# Adaptador_de_Iluminacao.net
KiCad netlist of a schematic drawn in EAGLE
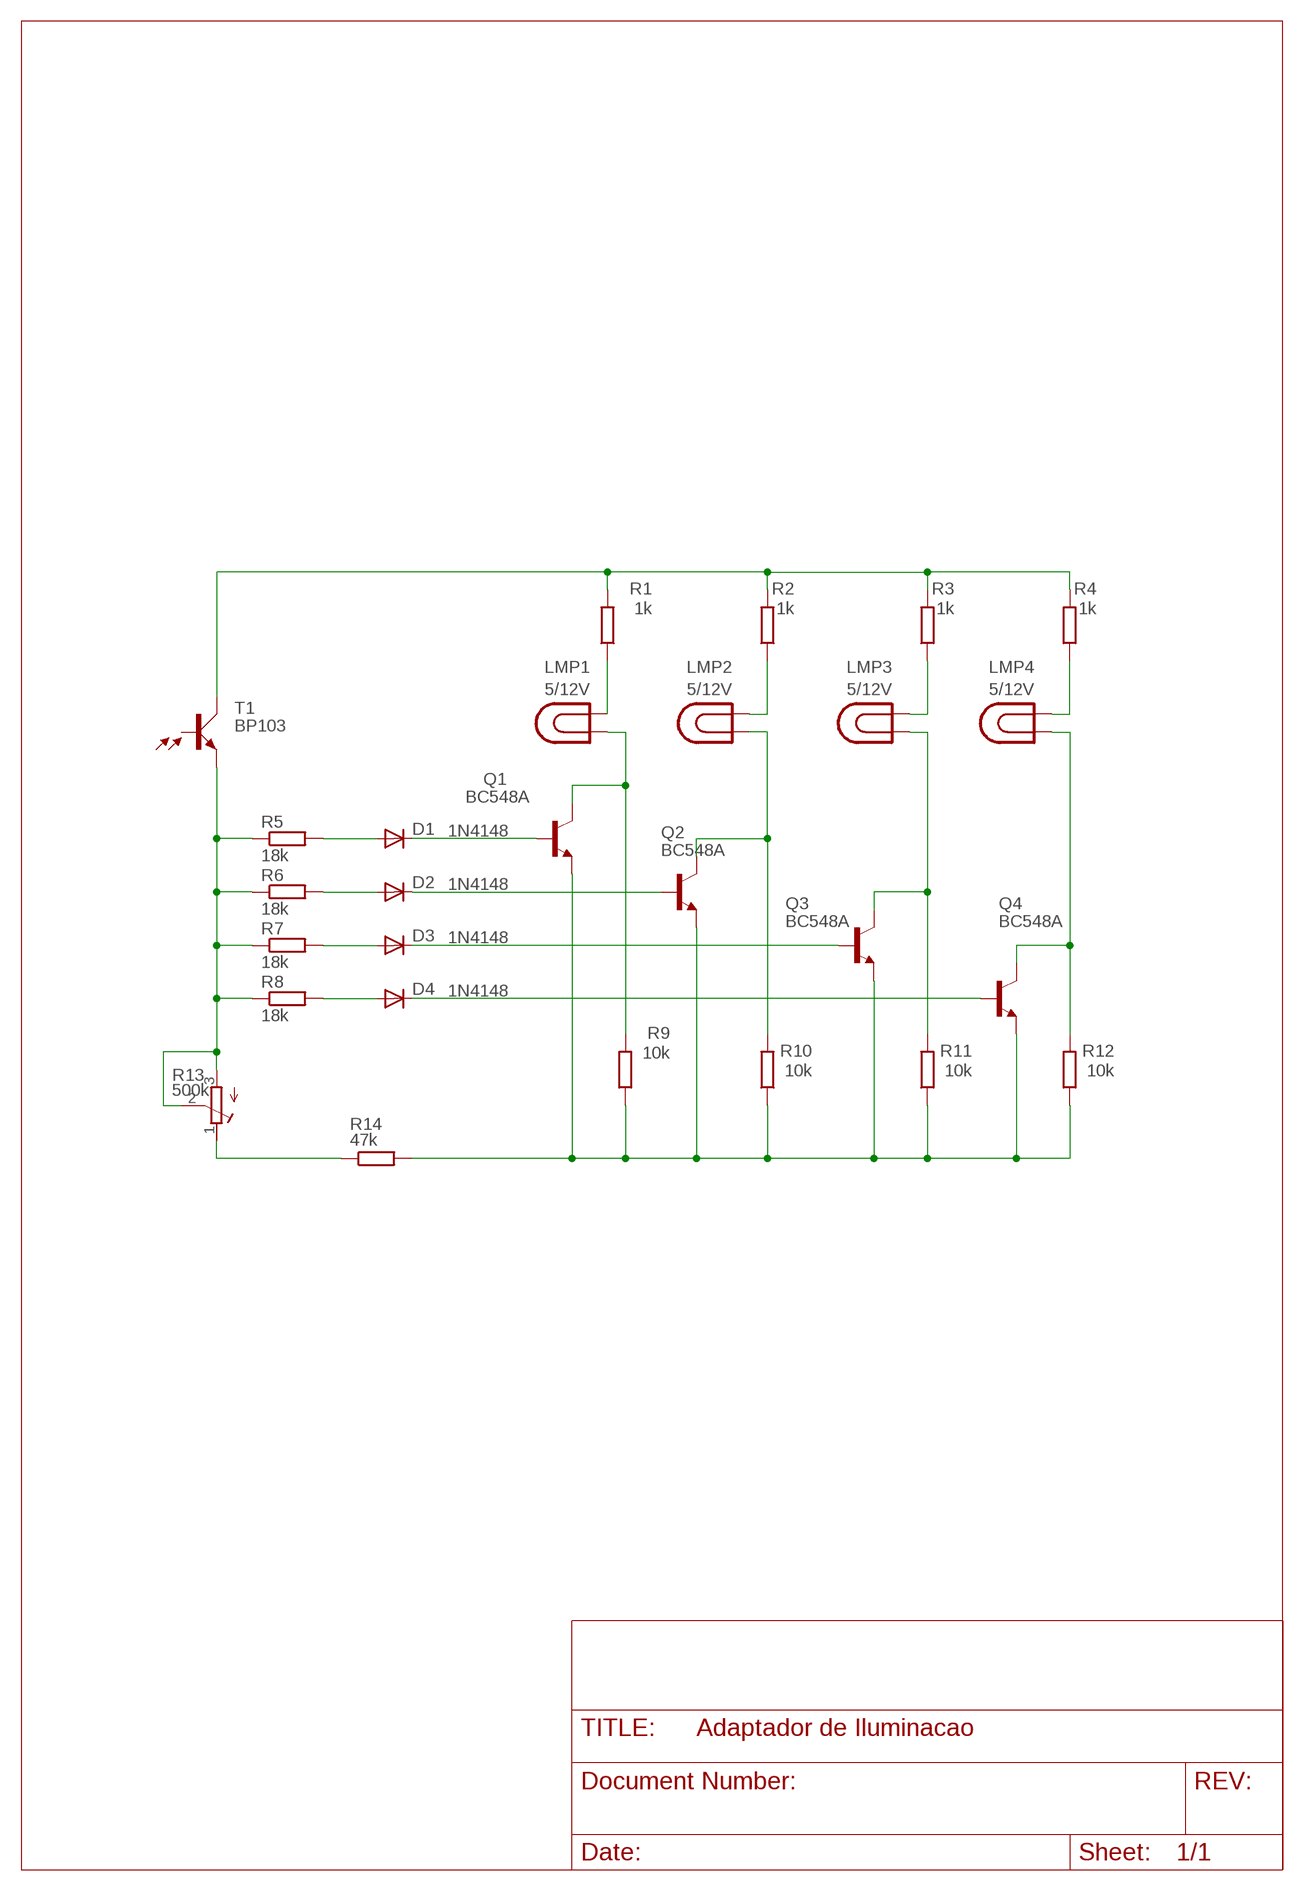
[diagram p0: schematic, sheet 1]

(export (version "E")
  (design (tool "Eeschema 10.0.6"))
  (components
    (comp (ref "D1")
      (value "1N4148")
      (footprint "eagle-import:DO35-7")
      (libsource (lib "eagle-import") (part "1N4148DO35-7"))
    )
    (comp (ref "D2")
      (value "1N4148")
      (footprint "eagle-import:DO35-7")
      (libsource (lib "eagle-import") (part "1N4148DO35-7"))
    )
    (comp (ref "D3")
      (value "1N4148")
      (footprint "eagle-import:DO35-7")
      (libsource (lib "eagle-import") (part "1N4148DO35-7"))
    )
    (comp (ref "D4")
      (value "1N4148")
      (footprint "eagle-import:DO35-7")
      (libsource (lib "eagle-import") (part "1N4148DO35-7"))
    )
    (comp (ref "LMP1")
      (value "5/12V")
      (footprint "eagle-import:LDH-5R")
      (libsource (lib "eagle-import") (part "LAMP"))
    )
    (comp (ref "LMP2")
      (value "5/12V")
      (footprint "eagle-import:LDH-5R")
      (libsource (lib "eagle-import") (part "LAMP"))
    )
    (comp (ref "LMP3")
      (value "5/12V")
      (footprint "eagle-import:LDH-5R")
      (libsource (lib "eagle-import") (part "LAMP"))
    )
    (comp (ref "LMP4")
      (value "5/12V")
      (footprint "eagle-import:LDH-5R")
      (libsource (lib "eagle-import") (part "LAMP"))
    )
    (comp (ref "Q1")
      (value "BC548A")
      (footprint "eagle-import:TO92-EBC")
      (libsource (lib "eagle-import") (part "BC548A"))
    )
    (comp (ref "Q2")
      (value "BC548A")
      (footprint "eagle-import:TO92-EBC")
      (libsource (lib "eagle-import") (part "BC548A"))
    )
    (comp (ref "Q3")
      (value "BC548A")
      (footprint "eagle-import:TO92-EBC")
      (libsource (lib "eagle-import") (part "BC548A"))
    )
    (comp (ref "Q4")
      (value "BC548A")
      (footprint "eagle-import:TO92-EBC")
      (libsource (lib "eagle-import") (part "BC548A"))
    )
    (comp (ref "R1")
      (value "1k")
      (footprint "eagle-import:0207_10")
      (libsource (lib "eagle-import") (part "R-EU_0207/10"))
    )
    (comp (ref "R2")
      (value "1k")
      (footprint "eagle-import:0207_10")
      (libsource (lib "eagle-import") (part "R-EU_0207/10"))
    )
    (comp (ref "R3")
      (value "1k")
      (footprint "eagle-import:0207_10")
      (libsource (lib "eagle-import") (part "R-EU_0207/10"))
    )
    (comp (ref "R4")
      (value "1k")
      (footprint "eagle-import:0207_10")
      (libsource (lib "eagle-import") (part "R-EU_0207/10"))
    )
    (comp (ref "R5")
      (value "18k")
      (footprint "eagle-import:0207_10")
      (libsource (lib "eagle-import") (part "R-EU_0207/10"))
    )
    (comp (ref "R6")
      (value "18k")
      (footprint "eagle-import:0207_10")
      (libsource (lib "eagle-import") (part "R-EU_0207/10"))
    )
    (comp (ref "R7")
      (value "18k")
      (footprint "eagle-import:0207_10")
      (libsource (lib "eagle-import") (part "R-EU_0207/10"))
    )
    (comp (ref "R8")
      (value "18k")
      (footprint "eagle-import:0207_10")
      (libsource (lib "eagle-import") (part "R-EU_0207/10"))
    )
    (comp (ref "R9")
      (value "10k")
      (footprint "eagle-import:0207_10")
      (libsource (lib "eagle-import") (part "R-EU_0207/10"))
    )
    (comp (ref "R10")
      (value "10k")
      (footprint "eagle-import:0207_10")
      (libsource (lib "eagle-import") (part "R-EU_0207/10"))
    )
    (comp (ref "R11")
      (value "10k")
      (footprint "eagle-import:0207_10")
      (libsource (lib "eagle-import") (part "R-EU_0207/10"))
    )
    (comp (ref "R12")
      (value "10k")
      (footprint "eagle-import:0207_10")
      (libsource (lib "eagle-import") (part "R-EU_0207/10"))
    )
    (comp (ref "R13")
      (value "500k")
      (footprint "eagle-import:RTRIM43P")
      (libsource (lib "eagle-import") (part "R-TRIMM43P"))
    )
    (comp (ref "R14")
      (value "47k")
      (footprint "eagle-import:0207_10")
      (libsource (lib "eagle-import") (part "R-EU_0207/10"))
    )
    (comp (ref "T1")
      (value "BP103")
      (footprint "eagle-import:BP103")
      (libsource (lib "eagle-import") (part "BP103"))
    )
  )
  (nets
    (net (code "1") (name "Net-(D1-PadA)") (class "Default")
      (node (ref "D1") (pin "A") (pinfunction "A_A") (pintype "passive"))
      (node (ref "R5") (pin "2") (pinfunction "2_2") (pintype "passive"))
    )
    (net (code "2") (name "Net-(D1-PadC)") (class "Default")
      (node (ref "D1") (pin "C") (pinfunction "C_C") (pintype "passive"))
      (node (ref "Q1") (pin "B") (pinfunction "B_B") (pintype "passive"))
    )
    (net (code "3") (name "Net-(D2-PadA)") (class "Default")
      (node (ref "D2") (pin "A") (pinfunction "A_A") (pintype "passive"))
      (node (ref "R6") (pin "2") (pinfunction "2_2") (pintype "passive"))
    )
    (net (code "4") (name "Net-(D2-PadC)") (class "Default")
      (node (ref "D2") (pin "C") (pinfunction "C_C") (pintype "passive"))
      (node (ref "Q2") (pin "B") (pinfunction "B_B") (pintype "passive"))
    )
    (net (code "5") (name "Net-(D3-PadA)") (class "Default")
      (node (ref "D3") (pin "A") (pinfunction "A_A") (pintype "passive"))
      (node (ref "R7") (pin "2") (pinfunction "2_2") (pintype "passive"))
    )
    (net (code "6") (name "Net-(D3-PadC)") (class "Default")
      (node (ref "D3") (pin "C") (pinfunction "C_C") (pintype "passive"))
      (node (ref "Q3") (pin "B") (pinfunction "B_B") (pintype "passive"))
    )
    (net (code "7") (name "Net-(D4-PadA)") (class "Default")
      (node (ref "D4") (pin "A") (pinfunction "A_A") (pintype "passive"))
      (node (ref "R8") (pin "2") (pinfunction "2_2") (pintype "passive"))
    )
    (net (code "8") (name "Net-(D4-PadC)") (class "Default")
      (node (ref "D4") (pin "C") (pinfunction "C_C") (pintype "passive"))
      (node (ref "Q4") (pin "B") (pinfunction "B_B") (pintype "passive"))
    )
    (net (code "9") (name "Net-(LMP1-Pad1)") (class "Default")
      (node (ref "LMP1") (pin "1") (pinfunction "1_1") (pintype "passive"))
      (node (ref "Q1") (pin "C") (pinfunction "C_C") (pintype "passive"))
      (node (ref "R9") (pin "2") (pinfunction "2_2") (pintype "passive"))
    )
    (net (code "10") (name "Net-(LMP1-Pad2)") (class "Default")
      (node (ref "LMP1") (pin "2") (pinfunction "2_2") (pintype "passive"))
      (node (ref "R1") (pin "1") (pinfunction "1_1") (pintype "passive"))
    )
    (net (code "11") (name "Net-(LMP2-Pad1)") (class "Default")
      (node (ref "LMP2") (pin "1") (pinfunction "1_1") (pintype "passive"))
      (node (ref "Q2") (pin "C") (pinfunction "C_C") (pintype "passive"))
      (node (ref "R10") (pin "2") (pinfunction "2_2") (pintype "passive"))
    )
    (net (code "12") (name "Net-(LMP2-Pad2)") (class "Default")
      (node (ref "LMP2") (pin "2") (pinfunction "2_2") (pintype "passive"))
      (node (ref "R2") (pin "1") (pinfunction "1_1") (pintype "passive"))
    )
    (net (code "13") (name "Net-(LMP3-Pad1)") (class "Default")
      (node (ref "LMP3") (pin "1") (pinfunction "1_1") (pintype "passive"))
      (node (ref "Q3") (pin "C") (pinfunction "C_C") (pintype "passive"))
      (node (ref "R11") (pin "2") (pinfunction "2_2") (pintype "passive"))
    )
    (net (code "14") (name "Net-(LMP3-Pad2)") (class "Default")
      (node (ref "LMP3") (pin "2") (pinfunction "2_2") (pintype "passive"))
      (node (ref "R3") (pin "1") (pinfunction "1_1") (pintype "passive"))
    )
    (net (code "15") (name "Net-(LMP4-Pad1)") (class "Default")
      (node (ref "LMP4") (pin "1") (pinfunction "1_1") (pintype "passive"))
      (node (ref "Q4") (pin "C") (pinfunction "C_C") (pintype "passive"))
      (node (ref "R12") (pin "2") (pinfunction "2_2") (pintype "passive"))
    )
    (net (code "16") (name "Net-(LMP4-Pad2)") (class "Default")
      (node (ref "LMP4") (pin "2") (pinfunction "2_2") (pintype "passive"))
      (node (ref "R4") (pin "1") (pinfunction "1_1") (pintype "passive"))
    )
    (net (code "17") (name "Net-(Q1-PadE)") (class "Default")
      (node (ref "Q1") (pin "E") (pinfunction "E_E") (pintype "passive"))
      (node (ref "Q2") (pin "E") (pinfunction "E_E") (pintype "passive"))
      (node (ref "Q3") (pin "E") (pinfunction "E_E") (pintype "passive"))
      (node (ref "Q4") (pin "E") (pinfunction "E_E") (pintype "passive"))
      (node (ref "R10") (pin "1") (pinfunction "1_1") (pintype "passive"))
      (node (ref "R11") (pin "1") (pinfunction "1_1") (pintype "passive"))
      (node (ref "R12") (pin "1") (pinfunction "1_1") (pintype "passive"))
      (node (ref "R14") (pin "2") (pinfunction "2_2") (pintype "passive"))
      (node (ref "R9") (pin "1") (pinfunction "1_1") (pintype "passive"))
    )
    (net (code "18") (name "Net-(R1-Pad2)") (class "Default")
      (node (ref "R1") (pin "2") (pinfunction "2_2") (pintype "passive"))
      (node (ref "R2") (pin "2") (pinfunction "2_2") (pintype "passive"))
      (node (ref "R3") (pin "2") (pinfunction "2_2") (pintype "passive"))
      (node (ref "R4") (pin "2") (pinfunction "2_2") (pintype "passive"))
      (node (ref "T1") (pin "C") (pinfunction "C_C") (pintype "passive"))
    )
    (net (code "19") (name "Net-(R13-A)") (class "Default")
      (node (ref "R13") (pin "2") (pinfunction "S_2") (pintype "passive"))
      (node (ref "R13") (pin "3") (pinfunction "A_3") (pintype "passive"))
      (node (ref "R5") (pin "1") (pinfunction "1_1") (pintype "passive"))
      (node (ref "R6") (pin "1") (pinfunction "1_1") (pintype "passive"))
      (node (ref "R7") (pin "1") (pinfunction "1_1") (pintype "passive"))
      (node (ref "R8") (pin "1") (pinfunction "1_1") (pintype "passive"))
      (node (ref "T1") (pin "E") (pinfunction "E_E") (pintype "passive"))
    )
    (net (code "20") (name "Net-(R13-E)") (class "Default")
      (node (ref "R13") (pin "1") (pinfunction "E_1") (pintype "passive"))
      (node (ref "R14") (pin "1") (pinfunction "1_1") (pintype "passive"))
    )
    (net (code "21") (name "unconnected-(T1-PadB)") (class "Default")
      (node (ref "T1") (pin "B") (pinfunction "B_B") (pintype "passive"))
    )
  )
)
